# OLM-base_v0_8.net
KiCad netlist of a schematic drawn in EAGLE
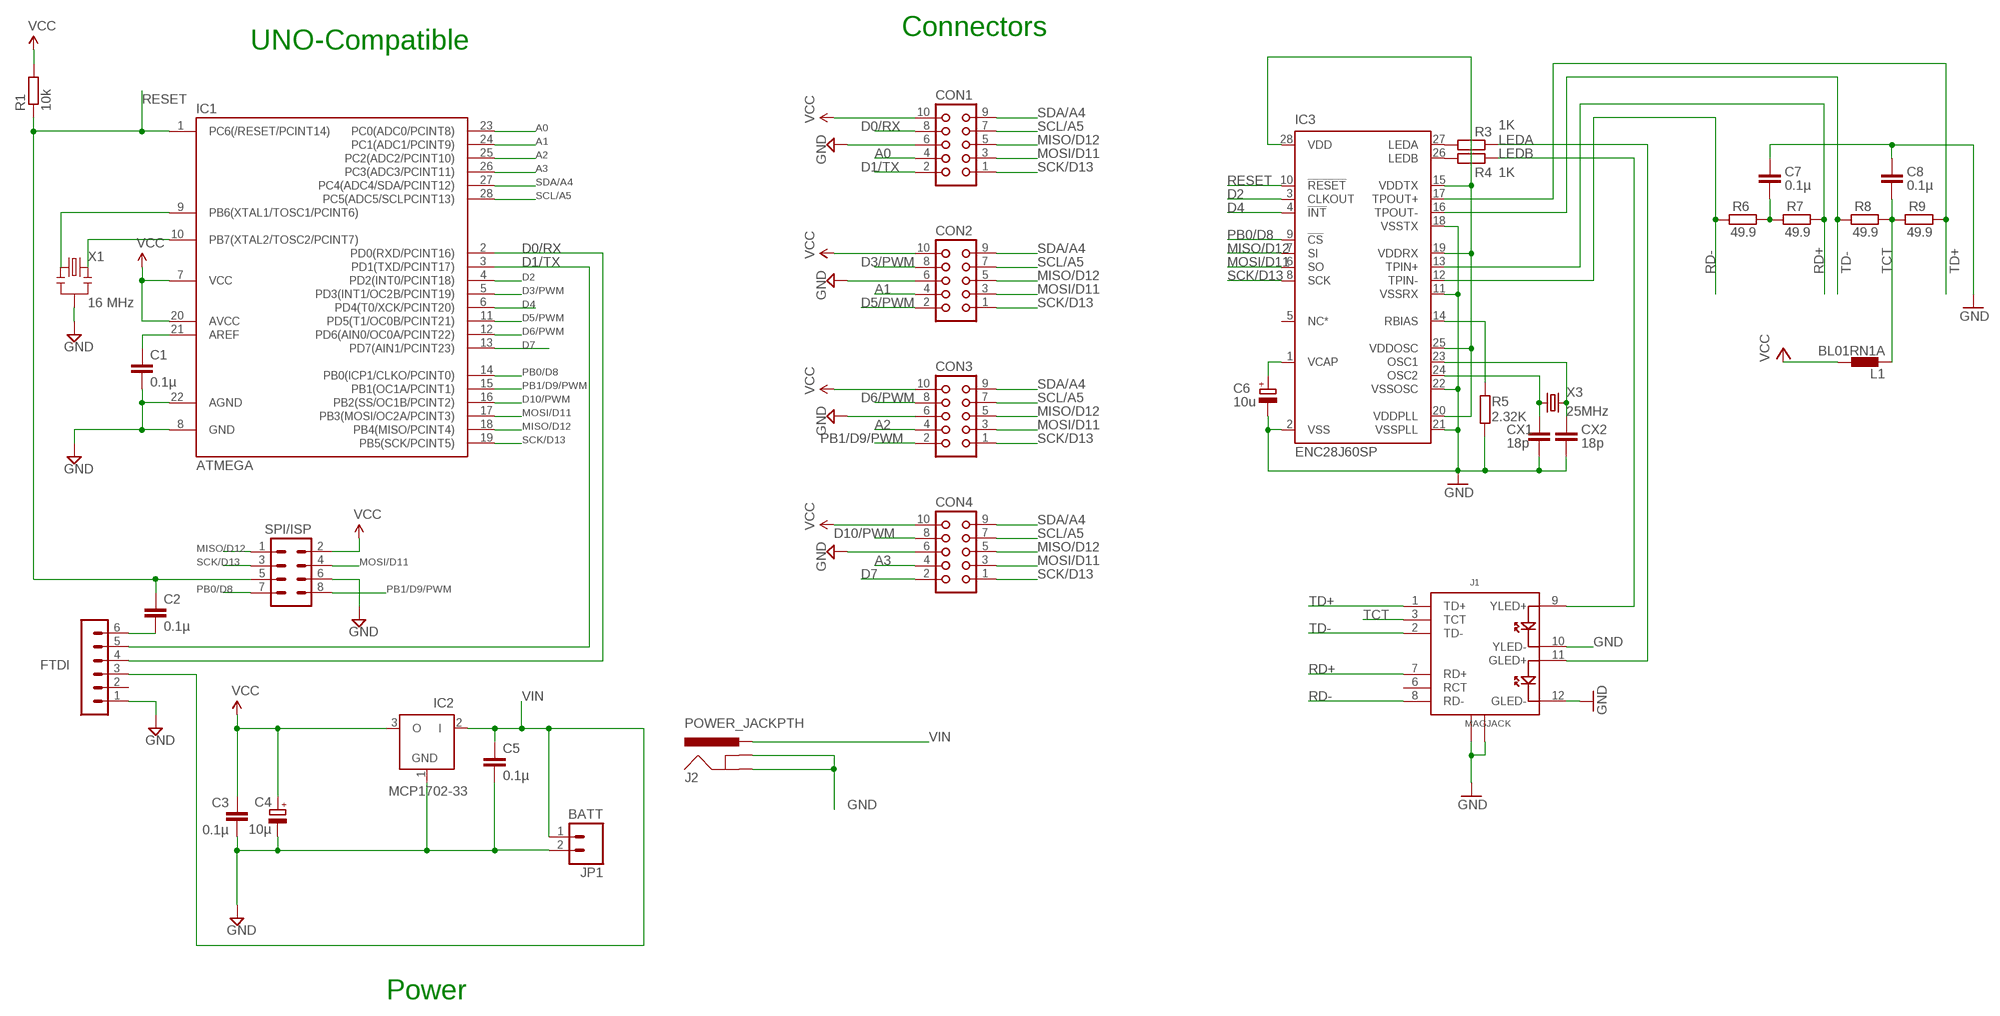
[diagram p0: schematic, sheet 1]

(export (version "E")
  (design (tool "Eeschema 10.0.6"))
  (components
    (comp (ref "C1")
      (value "0.1µ")
      (footprint "eagle-import:C025-024X044")
      (libsource (lib "eagle-import") (part "C-EU025-024X044"))
    )
    (comp (ref "C2")
      (value "0.1µ")
      (footprint "eagle-import:C025-024X044")
      (libsource (lib "eagle-import") (part "C-EU025-024X044"))
    )
    (comp (ref "C3")
      (value "0.1µ")
      (footprint "eagle-import:C025-024X044")
      (libsource (lib "eagle-import") (part "C-EU025-024X044"))
    )
    (comp (ref "C4")
      (value "10µ")
      (footprint "eagle-import:E1,8-4")
      (libsource (lib "eagle-import") (part "CPOL-EUE1.8-4"))
    )
    (comp (ref "C5")
      (value "0.1µ")
      (footprint "eagle-import:C025-024X044")
      (libsource (lib "eagle-import") (part "C-EU025-024X044"))
    )
    (comp (ref "C6")
      (value "10u")
      (footprint "eagle-import:E1,8-4")
      (libsource (lib "eagle-import") (part "CPOL-EUE1.8-4"))
    )
    (comp (ref "C7")
      (value "0.1µ")
      (footprint "eagle-import:C025-024X044")
      (libsource (lib "eagle-import") (part "C-EU025-024X044"))
    )
    (comp (ref "C8")
      (value "0.1µ")
      (footprint "eagle-import:C025-024X044")
      (libsource (lib "eagle-import") (part "C-EU025-024X044"))
    )
    (comp (ref "CON1")
      (value "CON10L")
      (footprint "eagle-import:CON10L")
      (libsource (lib "eagle-import") (part "CON10L"))
    )
    (comp (ref "CON2")
      (value "CON10L")
      (footprint "eagle-import:CON10L")
      (libsource (lib "eagle-import") (part "CON10L"))
    )
    (comp (ref "CON3")
      (value "CON10L")
      (footprint "eagle-import:CON10L")
      (libsource (lib "eagle-import") (part "CON10L"))
    )
    (comp (ref "CON4")
      (value "CON10L")
      (footprint "eagle-import:CON10L")
      (libsource (lib "eagle-import") (part "CON10L"))
    )
    (comp (ref "CX1")
      (value "18p")
      (footprint "eagle-import:C025-024X044")
      (libsource (lib "eagle-import") (part "C-EU025-024X044"))
    )
    (comp (ref "CX2")
      (value "18p")
      (footprint "eagle-import:C025-024X044")
      (libsource (lib "eagle-import") (part "C-EU025-024X044"))
    )
    (comp (ref "FTDI")
      (value "FTDI")
      (footprint "eagle-import:MA06-1")
      (libsource (lib "eagle-import") (part "MA06-1"))
    )
    (comp (ref "IC1")
      (value "ATMEGA")
      (footprint "eagle-import:DIL28-3")
      (libsource (lib "eagle-import") (part "ATMEGA48/88/168-PU"))
    )
    (comp (ref "IC2")
      (value "MCP1702-33")
      (footprint "eagle-import:TO92")
      (libsource (lib "eagle-import") (part "MCP1702Z"))
    )
    (comp (ref "IC3")
      (value "ENC28J60SP")
      (footprint "eagle-import:DIL28-3")
      (fields (field (name "MF") "MICROCHIP") (field (name "MPN") "ENC28J60/SP"))
      (libsource (lib "eagle-import") (part "ENC28J60SP"))
    )
    (comp (ref "J1")
      (value "MAGJACK")
      (footprint "eagle-import:MAGJACK")
      (libsource (lib "eagle-import") (part "MAGJACK"))
    )
    (comp (ref "J2")
      (value "POWER_JACKPTH")
      (footprint "eagle-import:POWER_JACK_PTH")
      (libsource (lib "eagle-import") (part "POWER_JACKPTH"))
    )
    (comp (ref "JP1")
      (value "BATT")
      (footprint "eagle-import:1X02_LOCK_LONGPADS")
      (libsource (lib "eagle-import") (part "M02LOCK_LONGPADS"))
    )
    (comp (ref "L1")
      (value "BL01RN1A")
      (footprint "eagle-import:BL01RN1A")
      (libsource (lib "eagle-import") (part "BL01RN1A"))
    )
    (comp (ref "R1")
      (value "10k")
      (footprint "eagle-import:0204_7")
      (libsource (lib "eagle-import") (part "resistor_R-EU_0204/7"))
    )
    (comp (ref "R3")
      (value "1K")
      (footprint "eagle-import:0204_7")
      (libsource (lib "eagle-import") (part "R-EU_0204/7"))
    )
    (comp (ref "R4")
      (value "1K")
      (footprint "eagle-import:0204_7")
      (libsource (lib "eagle-import") (part "R-EU_0204/7"))
    )
    (comp (ref "R5")
      (value "2.32K")
      (footprint "eagle-import:0204_7")
      (libsource (lib "eagle-import") (part "R-EU_0204/7"))
    )
    (comp (ref "R6")
      (value "49.9")
      (footprint "eagle-import:0204_7")
      (libsource (lib "eagle-import") (part "R-EU_0204/7"))
    )
    (comp (ref "R7")
      (value "49.9")
      (footprint "eagle-import:0204_7")
      (libsource (lib "eagle-import") (part "R-EU_0204/7"))
    )
    (comp (ref "R8")
      (value "49.9")
      (footprint "eagle-import:0204_7")
      (libsource (lib "eagle-import") (part "R-EU_0204/7"))
    )
    (comp (ref "R9")
      (value "49.9")
      (footprint "eagle-import:0204_7")
      (libsource (lib "eagle-import") (part "R-EU_0204/7"))
    )
    (comp (ref "SV1")
      (value "SPI/ISP")
      (footprint "eagle-import:MA04-2")
      (libsource (lib "eagle-import") (part "MA04-2"))
    )
    (comp (ref "X1")
      (value "16 MHz")
      (footprint "eagle-import:RESONATOR-PTH")
      (libsource (lib "eagle-import") (part "RESONATORPTH"))
    )
    (comp (ref "X3")
      (value "25MHz")
      (footprint "eagle-import:HC49US")
      (libsource (lib "eagle-import") (part "CRYSTALHC49US"))
    )
  )
  (nets
    (net (code "1") (name "/A0") (class "Default")
      (node (ref "CON1") (pin "4") (pinfunction "4_4") (pintype "passive"))
      (node (ref "IC1") (pin "23") (pinfunction "PC0(ADC0/PCINT8)_23") (pintype "bidirectional"))
    )
    (net (code "2") (name "/A1") (class "Default")
      (node (ref "CON2") (pin "4") (pinfunction "4_4") (pintype "passive"))
      (node (ref "IC1") (pin "24") (pinfunction "PC1(ADC1/PCINT9)_24") (pintype "bidirectional"))
    )
    (net (code "3") (name "/A2") (class "Default")
      (node (ref "CON3") (pin "4") (pinfunction "4_4") (pintype "passive"))
      (node (ref "IC1") (pin "25") (pinfunction "PC2(ADC2/PCINT10)_25") (pintype "bidirectional"))
    )
    (net (code "4") (name "/A3") (class "Default")
      (node (ref "CON4") (pin "4") (pinfunction "4_4") (pintype "passive"))
      (node (ref "IC1") (pin "26") (pinfunction "PC3(ADC3/PCINT11)_26") (pintype "bidirectional"))
    )
    (net (code "5") (name "/D0{slash}RX") (class "Default")
      (node (ref "CON1") (pin "8") (pinfunction "8_8") (pintype "passive"))
      (node (ref "FTDI") (pin "4") (pinfunction "4_4") (pintype "passive"))
      (node (ref "IC1") (pin "2") (pinfunction "PD0(RXD/PCINT16)_2") (pintype "bidirectional"))
    )
    (net (code "6") (name "/D1{slash}TX") (class "Default")
      (node (ref "CON1") (pin "2") (pinfunction "2_2") (pintype "passive"))
      (node (ref "FTDI") (pin "5") (pinfunction "5_5") (pintype "passive"))
      (node (ref "IC1") (pin "3") (pinfunction "PD1(TXD/PCINT17)_3") (pintype "bidirectional"))
    )
    (net (code "7") (name "/D2") (class "Default")
      (node (ref "IC1") (pin "4") (pinfunction "PD2(INT0/PCINT18)_4") (pintype "bidirectional"))
      (node (ref "IC3") (pin "3") (pinfunction "CLKOUT_3") (pintype "output"))
    )
    (net (code "8") (name "/D3{slash}PWM") (class "Default")
      (node (ref "CON2") (pin "8") (pinfunction "8_8") (pintype "passive"))
      (node (ref "IC1") (pin "5") (pinfunction "PD3(INT1/OC2B/PCINT19)_5") (pintype "bidirectional"))
    )
    (net (code "9") (name "/D4") (class "Default")
      (node (ref "IC1") (pin "6") (pinfunction "PD4(T0/XCK/PCINT20)_6") (pintype "bidirectional"))
      (node (ref "IC3") (pin "4") (pinfunction "~{INT}_4") (pintype "output"))
    )
    (net (code "10") (name "/D5{slash}PWM") (class "Default")
      (node (ref "CON2") (pin "2") (pinfunction "2_2") (pintype "passive"))
      (node (ref "IC1") (pin "11") (pinfunction "PD5(T1/OC0B/PCINT21)_11") (pintype "bidirectional"))
    )
    (net (code "11") (name "/D6{slash}PWM") (class "Default")
      (node (ref "CON3") (pin "8") (pinfunction "8_8") (pintype "passive"))
      (node (ref "IC1") (pin "12") (pinfunction "PD6(AIN0/OC0A/PCINT22)_12") (pintype "bidirectional"))
    )
    (net (code "12") (name "/D7") (class "Default")
      (node (ref "CON4") (pin "2") (pinfunction "2_2") (pintype "passive"))
      (node (ref "IC1") (pin "13") (pinfunction "PD7(AIN1/PCINT23)_13") (pintype "bidirectional"))
    )
    (net (code "13") (name "/D10{slash}PWM") (class "Default")
      (node (ref "CON4") (pin "8") (pinfunction "8_8") (pintype "passive"))
      (node (ref "IC1") (pin "16") (pinfunction "PB2(SS/OC1B/PCINT2)_16") (pintype "bidirectional"))
    )
    (net (code "14") (name "/LEDA") (class "Default")
      (node (ref "J1") (pin "11") (pinfunction "GLED+_11") (pintype "bidirectional"))
      (node (ref "R3") (pin "2") (pinfunction "2_2") (pintype "passive"))
    )
    (net (code "15") (name "/LEDB") (class "Default")
      (node (ref "J1") (pin "9") (pinfunction "YLED+_9") (pintype "bidirectional"))
      (node (ref "R4") (pin "2") (pinfunction "2_2") (pintype "passive"))
    )
    (net (code "16") (name "/MISO{slash}D12") (class "Default")
      (node (ref "CON1") (pin "5") (pinfunction "5_5") (pintype "passive"))
      (node (ref "CON2") (pin "5") (pinfunction "5_5") (pintype "passive"))
      (node (ref "CON3") (pin "5") (pinfunction "5_5") (pintype "passive"))
      (node (ref "CON4") (pin "5") (pinfunction "5_5") (pintype "passive"))
      (node (ref "IC1") (pin "18") (pinfunction "PB4(MISO/PCINT4)_18") (pintype "bidirectional"))
      (node (ref "IC3") (pin "7") (pinfunction "SI_7") (pintype "input"))
      (node (ref "SV1") (pin "1") (pinfunction "1_1") (pintype "passive"))
    )
    (net (code "17") (name "/MOSI{slash}D11") (class "Default")
      (node (ref "CON1") (pin "3") (pinfunction "3_3") (pintype "passive"))
      (node (ref "CON2") (pin "3") (pinfunction "3_3") (pintype "passive"))
      (node (ref "CON3") (pin "3") (pinfunction "3_3") (pintype "passive"))
      (node (ref "CON4") (pin "3") (pinfunction "3_3") (pintype "passive"))
      (node (ref "IC1") (pin "17") (pinfunction "PB3(MOSI/OC2A/PCINT3)_17") (pintype "bidirectional"))
      (node (ref "IC3") (pin "6") (pinfunction "SO_6") (pintype "output"))
      (node (ref "SV1") (pin "4") (pinfunction "4_4") (pintype "passive"))
    )
    (net (code "18") (name "/PB0{slash}D8") (class "Default")
      (node (ref "IC1") (pin "14") (pinfunction "PB0(ICP1/CLKO/PCINT0)_14") (pintype "bidirectional"))
      (node (ref "IC3") (pin "9") (pinfunction "~{CS}_9") (pintype "input"))
      (node (ref "SV1") (pin "7") (pinfunction "7_7") (pintype "passive"))
    )
    (net (code "19") (name "/PB1{slash}D9{slash}PWM") (class "Default")
      (node (ref "CON3") (pin "2") (pinfunction "2_2") (pintype "passive"))
      (node (ref "IC1") (pin "15") (pinfunction "PB1(OC1A/PCINT1)_15") (pintype "bidirectional"))
      (node (ref "SV1") (pin "8") (pinfunction "8_8") (pintype "passive"))
    )
    (net (code "20") (name "/RD+") (class "Default")
      (node (ref "IC3") (pin "13") (pinfunction "TPIN+_13") (pintype "input"))
      (node (ref "J1") (pin "7") (pinfunction "RD+_7") (pintype "bidirectional"))
      (node (ref "R7") (pin "2") (pinfunction "2_2") (pintype "passive"))
    )
    (net (code "21") (name "/RD-") (class "Default")
      (node (ref "IC3") (pin "12") (pinfunction "TPIN-_12") (pintype "input"))
      (node (ref "J1") (pin "8") (pinfunction "RD-_8") (pintype "bidirectional"))
      (node (ref "R6") (pin "1") (pinfunction "1_1") (pintype "passive"))
    )
    (net (code "22") (name "/RESET") (class "Default")
      (node (ref "C2") (pin "1") (pinfunction "1_1") (pintype "passive"))
      (node (ref "IC1") (pin "1") (pinfunction "PC6(/RESET/PCINT14)_1") (pintype "bidirectional"))
      (node (ref "IC3") (pin "10") (pinfunction "~{RESET}_10") (pintype "input"))
      (node (ref "R1") (pin "1") (pinfunction "1_1") (pintype "passive"))
      (node (ref "SV1") (pin "5") (pinfunction "5_5") (pintype "passive"))
    )
    (net (code "23") (name "/SCK{slash}D13") (class "Default")
      (node (ref "CON1") (pin "1") (pinfunction "1_1") (pintype "passive"))
      (node (ref "CON2") (pin "1") (pinfunction "1_1") (pintype "passive"))
      (node (ref "CON3") (pin "1") (pinfunction "1_1") (pintype "passive"))
      (node (ref "CON4") (pin "1") (pinfunction "1_1") (pintype "passive"))
      (node (ref "IC1") (pin "19") (pinfunction "PB5(SCK/PCINT5)_19") (pintype "bidirectional"))
      (node (ref "IC3") (pin "8") (pinfunction "SCK_8") (pintype "input"))
      (node (ref "SV1") (pin "3") (pinfunction "3_3") (pintype "passive"))
    )
    (net (code "24") (name "/SCL{slash}A5") (class "Default")
      (node (ref "CON1") (pin "7") (pinfunction "7_7") (pintype "passive"))
      (node (ref "CON2") (pin "7") (pinfunction "7_7") (pintype "passive"))
      (node (ref "CON3") (pin "7") (pinfunction "7_7") (pintype "passive"))
      (node (ref "CON4") (pin "7") (pinfunction "7_7") (pintype "passive"))
      (node (ref "IC1") (pin "28") (pinfunction "PC5(ADC5/SCLPCINT13)_28") (pintype "bidirectional"))
    )
    (net (code "25") (name "/SDA{slash}A4") (class "Default")
      (node (ref "CON1") (pin "9") (pinfunction "9_9") (pintype "passive"))
      (node (ref "CON2") (pin "9") (pinfunction "9_9") (pintype "passive"))
      (node (ref "CON3") (pin "9") (pinfunction "9_9") (pintype "passive"))
      (node (ref "CON4") (pin "9") (pinfunction "9_9") (pintype "passive"))
      (node (ref "IC1") (pin "27") (pinfunction "PC4(ADC4/SDA/PCINT12)_27") (pintype "bidirectional"))
    )
    (net (code "26") (name "/TCT") (class "Default")
      (node (ref "C8") (pin "2") (pinfunction "2_2") (pintype "passive"))
      (node (ref "J1") (pin "3") (pinfunction "TCT_3") (pintype "bidirectional"))
      (node (ref "L1") (pin "1") (pinfunction "1_1") (pintype "passive"))
      (node (ref "R8") (pin "2") (pinfunction "2_2") (pintype "passive"))
      (node (ref "R9") (pin "1") (pinfunction "1_1") (pintype "passive"))
    )
    (net (code "27") (name "/TD+") (class "Default")
      (node (ref "IC3") (pin "17") (pinfunction "TPOUT+_17") (pintype "output"))
      (node (ref "J1") (pin "1") (pinfunction "TD+_1") (pintype "bidirectional"))
      (node (ref "R9") (pin "2") (pinfunction "2_2") (pintype "passive"))
    )
    (net (code "28") (name "/TD-") (class "Default")
      (node (ref "IC3") (pin "16") (pinfunction "TPOUT-_16") (pintype "output"))
      (node (ref "J1") (pin "2") (pinfunction "TD-_2") (pintype "bidirectional"))
      (node (ref "R8") (pin "1") (pinfunction "1_1") (pintype "passive"))
    )
    (net (code "29") (name "/VIN") (class "Default")
      (node (ref "C5") (pin "1") (pinfunction "1_1") (pintype "passive"))
      (node (ref "FTDI") (pin "3") (pinfunction "3_3") (pintype "passive"))
      (node (ref "IC2") (pin "2") (pinfunction "I_2") (pintype "input"))
      (node (ref "J2") (pin "PWR") (pinfunction "PWR_PWR") (pintype "bidirectional"))
      (node (ref "JP1") (pin "1") (pinfunction "1_1") (pintype "passive"))
    )
    (net (code "30") (name "GND") (class "Default")
      (node (ref "C1") (pin "2") (pinfunction "2_2") (pintype "passive"))
      (node (ref "C3") (pin "2") (pinfunction "2_2") (pintype "passive"))
      (node (ref "C4") (pin "-") (pinfunction "-_-") (pintype "passive"))
      (node (ref "C5") (pin "2") (pinfunction "2_2") (pintype "passive"))
      (node (ref "C6") (pin "-") (pinfunction "-_-") (pintype "passive"))
      (node (ref "C7") (pin "1") (pinfunction "1_1") (pintype "passive"))
      (node (ref "C8") (pin "1") (pinfunction "1_1") (pintype "passive"))
      (node (ref "CON1") (pin "6") (pinfunction "6_6") (pintype "passive"))
      (node (ref "CON2") (pin "6") (pinfunction "6_6") (pintype "passive"))
      (node (ref "CON3") (pin "6") (pinfunction "6_6") (pintype "passive"))
      (node (ref "CON4") (pin "6") (pinfunction "6_6") (pintype "passive"))
      (node (ref "CX1") (pin "2") (pinfunction "2_2") (pintype "passive"))
      (node (ref "CX2") (pin "2") (pinfunction "2_2") (pintype "passive"))
      (node (ref "FTDI") (pin "1") (pinfunction "1_1") (pintype "passive"))
      (node (ref "IC1") (pin "22") (pinfunction "AGND_22") (pintype "power_in"))
      (node (ref "IC1") (pin "8") (pinfunction "GND_8") (pintype "power_in"))
      (node (ref "IC2") (pin "1") (pinfunction "GND_1") (pintype "power_in"))
      (node (ref "IC3") (pin "11") (pinfunction "VSSRX_11") (pintype "input"))
      (node (ref "IC3") (pin "18") (pinfunction "VSSTX_18") (pintype "input"))
      (node (ref "IC3") (pin "2") (pinfunction "VSS_2") (pintype "input"))
      (node (ref "IC3") (pin "21") (pinfunction "VSSPLL_21") (pintype "input"))
      (node (ref "IC3") (pin "22") (pinfunction "VSSOSC_22") (pintype "input"))
      (node (ref "J1") (pin "10") (pinfunction "YLED-_10") (pintype "bidirectional"))
      (node (ref "J1") (pin "12") (pinfunction "GLED-_12") (pintype "bidirectional"))
      (node (ref "J1") (pin "M1") (pinfunction "GND1_M1") (pintype "bidirectional"))
      (node (ref "J1") (pin "M2") (pinfunction "GND2_M2") (pintype "bidirectional"))
      (node (ref "J2") (pin "GND") (pinfunction "GND_GND") (pintype "bidirectional"))
      (node (ref "J2") (pin "GNDBREAK") (pinfunction "GNDBREAK_GNDBREAK") (pintype "bidirectional"))
      (node (ref "JP1") (pin "2") (pinfunction "2_2") (pintype "passive"))
      (node (ref "R5") (pin "2") (pinfunction "2_2") (pintype "passive"))
      (node (ref "SV1") (pin "6") (pinfunction "6_6") (pintype "passive"))
      (node (ref "X1") (pin "2") (pinfunction "2_2") (pintype "passive"))
    )
    (net (code "31") (name "Net-(C2-Pad2)") (class "Default")
      (node (ref "C2") (pin "2") (pinfunction "2_2") (pintype "passive"))
      (node (ref "FTDI") (pin "6") (pinfunction "6_6") (pintype "passive"))
    )
    (net (code "32") (name "Net-(C7-Pad2)") (class "Default")
      (node (ref "C7") (pin "2") (pinfunction "2_2") (pintype "passive"))
      (node (ref "R6") (pin "2") (pinfunction "2_2") (pintype "passive"))
      (node (ref "R7") (pin "1") (pinfunction "1_1") (pintype "passive"))
    )
    (net (code "33") (name "Net-(IC1-AREF)") (class "Default")
      (node (ref "C1") (pin "1") (pinfunction "1_1") (pintype "passive"))
      (node (ref "IC1") (pin "21") (pinfunction "AREF_21") (pintype "passive"))
    )
    (net (code "34") (name "Net-(IC1-PB6(XTAL1{slash}TOSC1{slash}PCINT6))") (class "Default")
      (node (ref "IC1") (pin "9") (pinfunction "PB6(XTAL1/TOSC1/PCINT6)_9") (pintype "bidirectional"))
      (node (ref "X1") (pin "1") (pinfunction "1_1") (pintype "passive"))
    )
    (net (code "35") (name "Net-(IC1-PB7(XTAL2{slash}TOSC2{slash}PCINT7))") (class "Default")
      (node (ref "IC1") (pin "10") (pinfunction "PB7(XTAL2/TOSC2/PCINT7)_10") (pintype "bidirectional"))
      (node (ref "X1") (pin "3") (pinfunction "3_3") (pintype "passive"))
    )
    (net (code "36") (name "Net-(IC3-LEDA)") (class "Default")
      (node (ref "IC3") (pin "27") (pinfunction "LEDA_27") (pintype "output"))
      (node (ref "R3") (pin "1") (pinfunction "1_1") (pintype "passive"))
    )
    (net (code "37") (name "Net-(IC3-LEDB)") (class "Default")
      (node (ref "IC3") (pin "26") (pinfunction "LEDB_26") (pintype "output"))
      (node (ref "R4") (pin "1") (pinfunction "1_1") (pintype "passive"))
    )
    (net (code "38") (name "Net-(IC3-OSC1)") (class "Default")
      (node (ref "CX2") (pin "1") (pinfunction "1_1") (pintype "passive"))
      (node (ref "IC3") (pin "23") (pinfunction "OSC1_23") (pintype "input"))
      (node (ref "X3") (pin "2") (pinfunction "2_2") (pintype "passive"))
    )
    (net (code "39") (name "Net-(IC3-OSC2)") (class "Default")
      (node (ref "CX1") (pin "1") (pinfunction "1_1") (pintype "passive"))
      (node (ref "IC3") (pin "24") (pinfunction "OSC2_24") (pintype "output"))
      (node (ref "X3") (pin "1") (pinfunction "1_1") (pintype "passive"))
    )
    (net (code "40") (name "Net-(IC3-RBIAS)") (class "Default")
      (node (ref "IC3") (pin "14") (pinfunction "RBIAS_14") (pintype "input"))
      (node (ref "R5") (pin "1") (pinfunction "1_1") (pintype "passive"))
    )
    (net (code "41") (name "Net-(IC3-VCAP)") (class "Default")
      (node (ref "C6") (pin "+") (pinfunction "+_+") (pintype "passive"))
      (node (ref "IC3") (pin "1") (pinfunction "VCAP_1") (pintype "input"))
    )
    (net (code "42") (name "VCC") (class "Default")
      (node (ref "C3") (pin "1") (pinfunction "1_1") (pintype "passive"))
      (node (ref "C4") (pin "+") (pinfunction "+_+") (pintype "passive"))
      (node (ref "CON1") (pin "10") (pinfunction "10_10") (pintype "passive"))
      (node (ref "CON2") (pin "10") (pinfunction "10_10") (pintype "passive"))
      (node (ref "CON3") (pin "10") (pinfunction "10_10") (pintype "passive"))
      (node (ref "CON4") (pin "10") (pinfunction "10_10") (pintype "passive"))
      (node (ref "IC1") (pin "20") (pinfunction "AVCC_20") (pintype "passive"))
      (node (ref "IC1") (pin "7") (pinfunction "VCC_7") (pintype "power_in"))
      (node (ref "IC2") (pin "3") (pinfunction "O_3") (pintype "input"))
      (node (ref "IC3") (pin "15") (pinfunction "VDDTX_15") (pintype "input"))
      (node (ref "IC3") (pin "19") (pinfunction "VDDRX_19") (pintype "input"))
      (node (ref "IC3") (pin "20") (pinfunction "VDDPLL_20") (pintype "input"))
      (node (ref "IC3") (pin "25") (pinfunction "VDDOSC_25") (pintype "input"))
      (node (ref "IC3") (pin "28") (pinfunction "VDD_28") (pintype "input"))
      (node (ref "L1") (pin "2") (pinfunction "2_2") (pintype "passive"))
      (node (ref "R1") (pin "2") (pinfunction "2_2") (pintype "passive"))
      (node (ref "SV1") (pin "2") (pinfunction "2_2") (pintype "passive"))
    )
    (net (code "43") (name "unconnected-(FTDI-Pad2)") (class "Default")
      (node (ref "FTDI") (pin "2") (pinfunction "2_2") (pintype "passive"))
    )
    (net (code "44") (name "unconnected-(IC3-NC*-Pad5)") (class "Default")
      (node (ref "IC3") (pin "5") (pinfunction "NC*_5") (pintype "output"))
    )
    (net (code "45") (name "unconnected-(J1-RCT-Pad6)") (class "Default")
      (node (ref "J1") (pin "6") (pinfunction "RCT_6") (pintype "bidirectional"))
    )
  )
)
